# 01_MAIN.net
KiCad netlist of a schematic drawn in Altium Designer
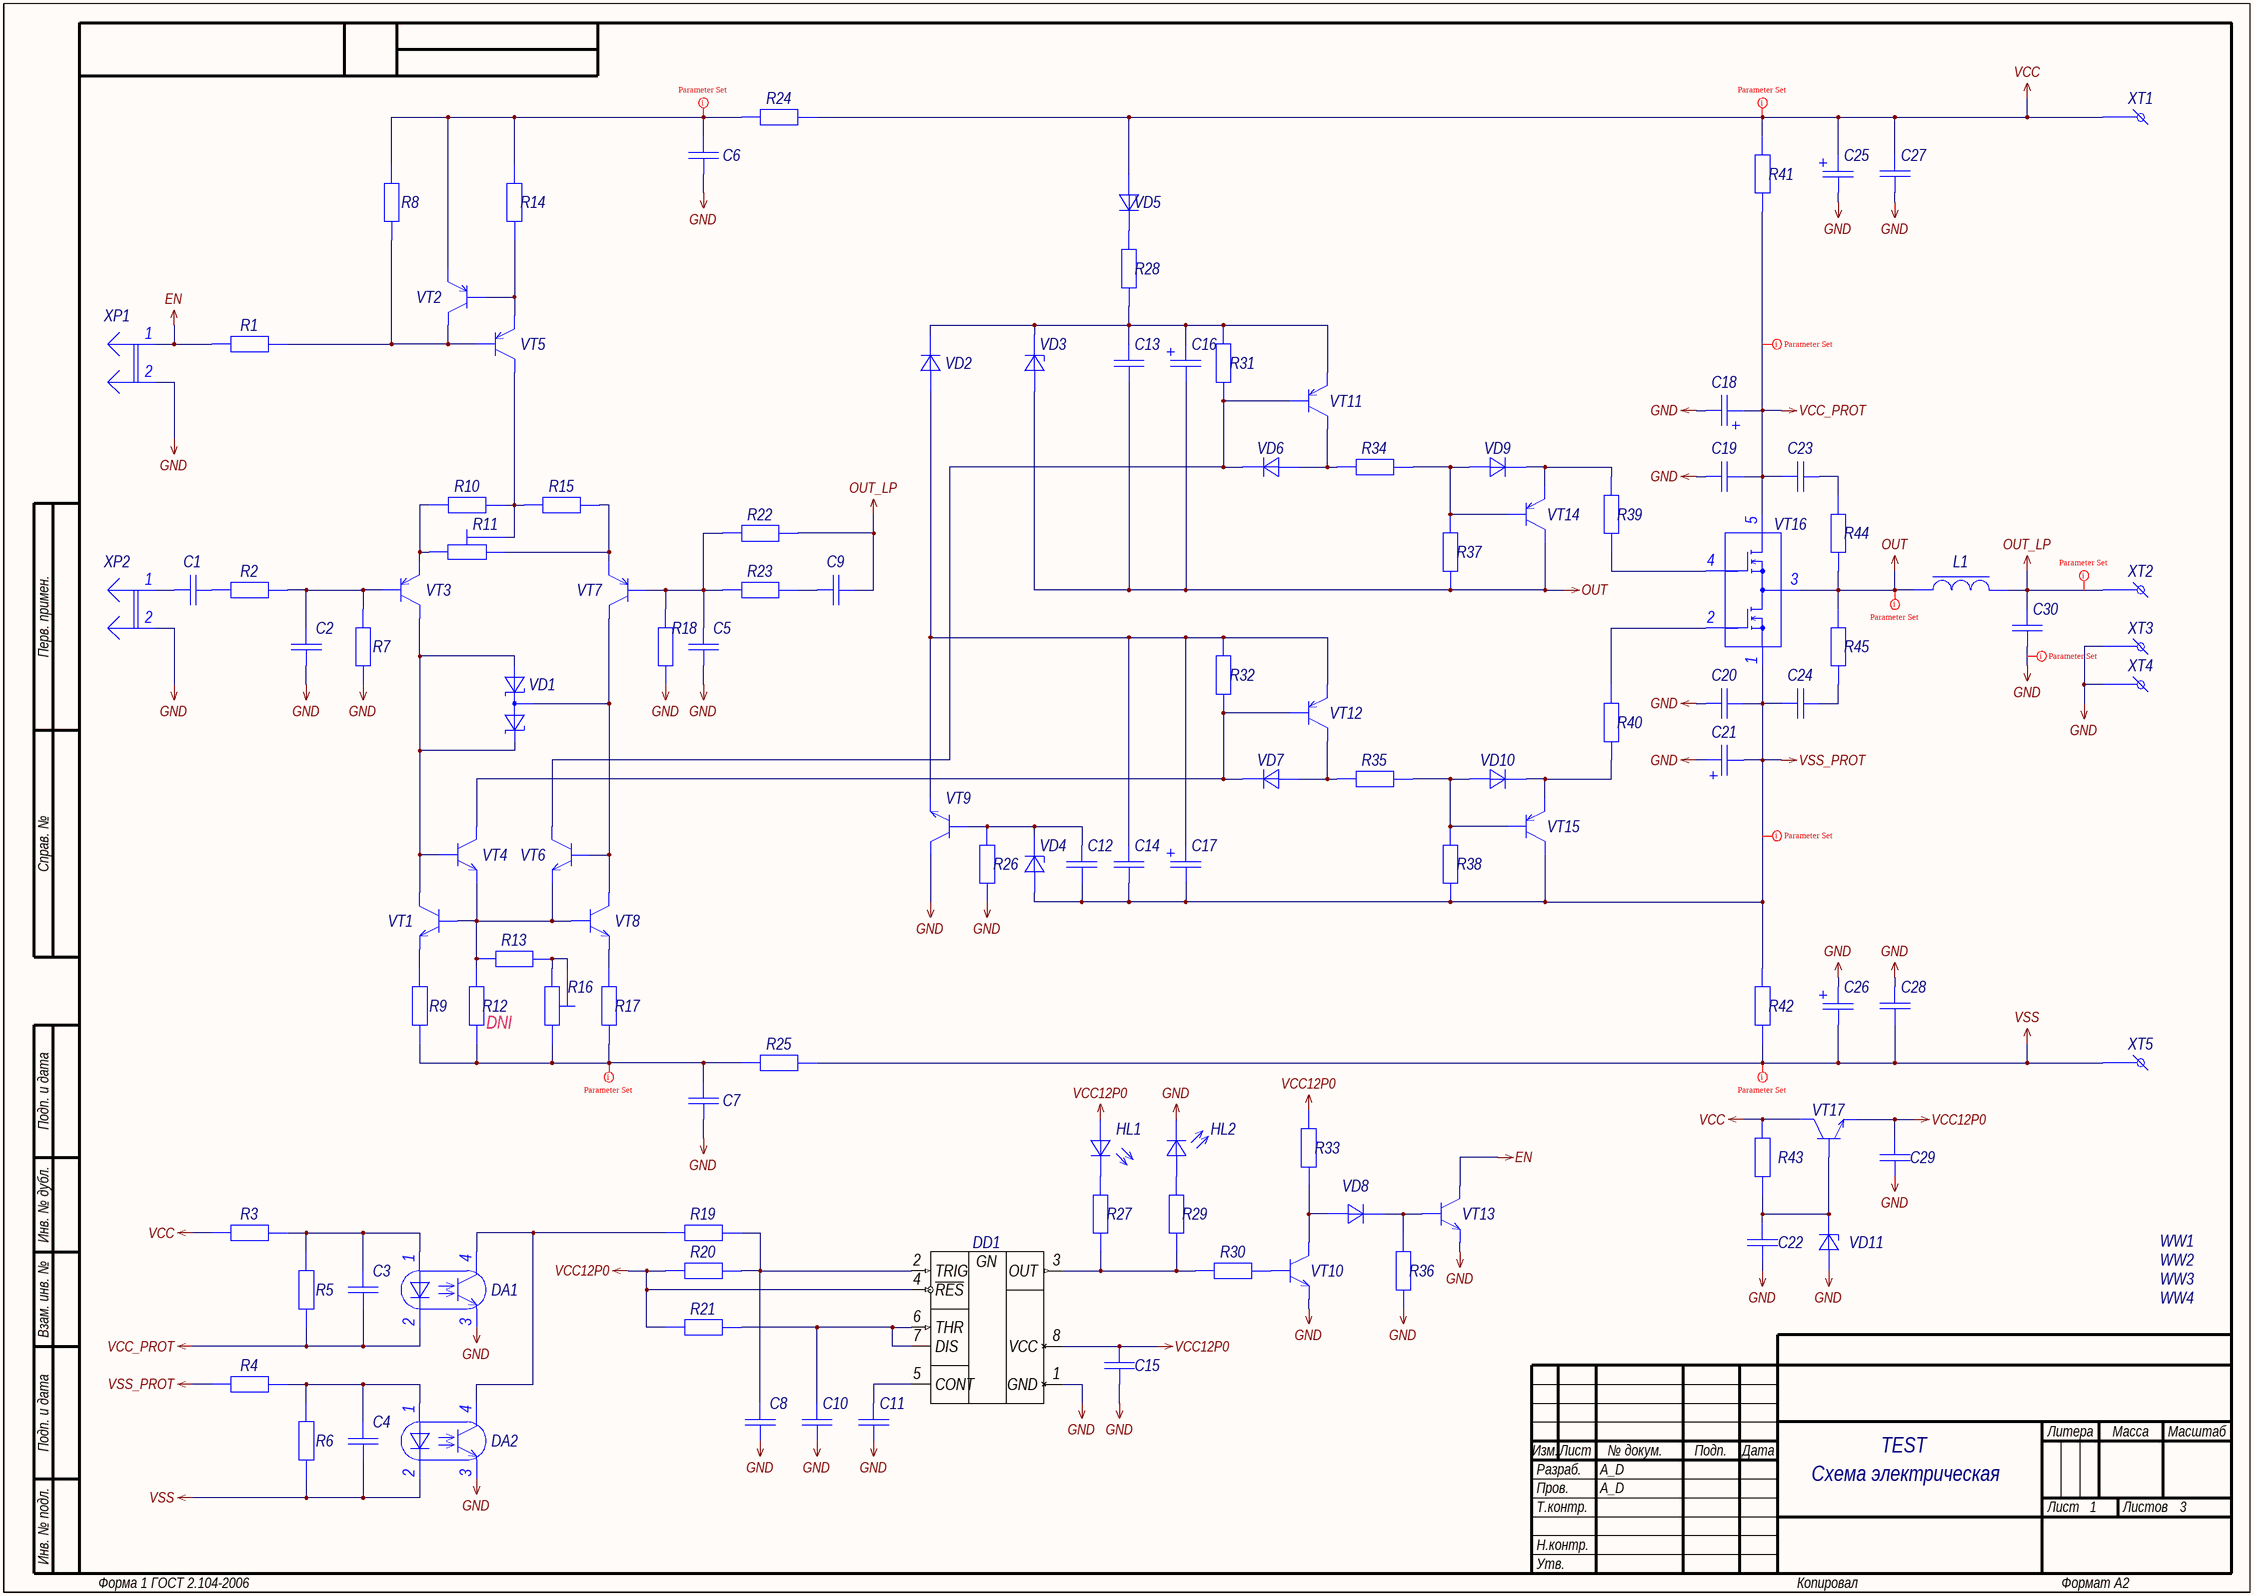
[diagram p0: 01_MAIN.SchDoc]

(export (version "E")
  (design (tool "Eeschema 10.0.6"))
  (components
    (comp (ref "C1")
      (value "Capacitor")
      (footprint "CAPF_050D500P720X500X1000")
      (fields
        (field (name "PART NUMBER") "MKS2B042201F00JSSD")
        (field (name "VOLTAGE") "50V")
        (field (name "TOLERANCE") "±5%")
      )
      (libsource (lib "ADLib") (part "Capacitor"))
    )
    (comp (ref "C2")
      (value "Capacitor")
      (footprint "CAPF_050D500P720X450X600")
      (fields
        (field (name "PART NUMBER") "FKP2D001001D00JSSD")
        (field (name "VOLTAGE") "100V")
        (field (name "TOLERANCE") "±5%")
      )
      (libsource (lib "ADLib") (part "Capacitor"))
    )
    (comp (ref "C3")
      (value "Capacitor")
      (footprint "C0603_L")
      (fields
        (field (name "PART NUMBER") "GRM188R71H182JA01D")
        (field (name "VOLTAGE") "50V")
        (field (name "TOLERANCE") "±5%")
      )
      (libsource (lib "ADLib") (part "Capacitor"))
    )
    (comp (ref "C4")
      (value "Capacitor")
      (footprint "C0603_L")
      (fields
        (field (name "PART NUMBER") "GRM188R71H182JA01D")
        (field (name "VOLTAGE") "50V")
        (field (name "TOLERANCE") "±5%")
      )
      (libsource (lib "ADLib") (part "Capacitor"))
    )
    (comp (ref "C5")
      (value "Capacitor")
      (footprint "C0603_L")
      (fields
        (field (name "PART NUMBER") "GRM1885C1H220JA01D")
        (field (name "VOLTAGE") "50V")
        (field (name "TOLERANCE") "±5%")
      )
      (libsource (lib "ADLib") (part "Capacitor"))
    )
    (comp (ref "C6")
      (value "Capacitor")
      (footprint "C0805_L")
      (fields
        (field (name "PART NUMBER") "GCJ21BR72A104KA01L")
        (field (name "VOLTAGE") "100V")
        (field (name "TOLERANCE") "±10%")
      )
      (libsource (lib "ADLib") (part "Capacitor"))
    )
    (comp (ref "C7")
      (value "Capacitor")
      (footprint "C0805_L")
      (fields
        (field (name "PART NUMBER") "GCJ21BR72A104KA01L")
        (field (name "VOLTAGE") "100V")
        (field (name "TOLERANCE") "±10%")
      )
      (libsource (lib "ADLib") (part "Capacitor"))
    )
    (comp (ref "C8")
      (value "Capacitor")
      (footprint "C0603_L")
      (fields
        (field (name "PART NUMBER") "GCJ188R71C474KA12D")
        (field (name "VOLTAGE") "16V")
        (field (name "TOLERANCE") "±10%")
      )
      (libsource (lib "ADLib") (part "Capacitor"))
    )
    (comp (ref "C9")
      (value "Capacitor")
      (footprint "C0603_L")
      (fields
        (field (name "PART NUMBER") "GRM1885C1H220JA01D")
        (field (name "VOLTAGE") "50V")
        (field (name "TOLERANCE") "±5%")
      )
      (libsource (lib "ADLib") (part "Capacitor"))
    )
    (comp (ref "C10")
      (value "Capacitor")
      (footprint "C0603_L")
      (fields
        (field (name "PART NUMBER") "GCM188R71E105KA64D")
        (field (name "VOLTAGE") "25V")
        (field (name "TOLERANCE") "±10%")
      )
      (libsource (lib "ADLib") (part "Capacitor"))
    )
    (comp (ref "C11")
      (value "Capacitor")
      (footprint "C0603_L")
      (fields
        (field (name "PART NUMBER") "GCM188R71E105KA64D")
        (field (name "VOLTAGE") "25V")
        (field (name "TOLERANCE") "±10%")
      )
      (libsource (lib "ADLib") (part "Capacitor"))
    )
    (comp (ref "C12")
      (value "Capacitor")
      (footprint "C0603_L")
      (fields
        (field (name "PART NUMBER") "GCM188R71E105KA64D")
        (field (name "VOLTAGE") "25V")
        (field (name "TOLERANCE") "±10%")
      )
      (libsource (lib "ADLib") (part "Capacitor"))
    )
    (comp (ref "C13")
      (value "Capacitor")
      (footprint "C0805_L")
      (fields
        (field (name "PART NUMBER") "GCJ21BR72A104KA01L")
        (field (name "VOLTAGE") "100V")
        (field (name "TOLERANCE") "±10%")
      )
      (libsource (lib "ADLib") (part "Capacitor"))
    )
    (comp (ref "C14")
      (value "Capacitor")
      (footprint "C0805_L")
      (fields
        (field (name "PART NUMBER") "GCJ21BR72A104KA01L")
        (field (name "VOLTAGE") "100V")
        (field (name "TOLERANCE") "±10%")
      )
      (libsource (lib "ADLib") (part "Capacitor"))
    )
    (comp (ref "C15")
      (value "Capacitor")
      (footprint "C0603_L")
      (fields
        (field (name "PART NUMBER") "GCJ188R71C474KA12D")
        (field (name "VOLTAGE") "16V")
        (field (name "TOLERANCE") "±10%")
      )
      (libsource (lib "ADLib") (part "Capacitor"))
    )
    (comp (ref "C16")
      (value "Capacitor-E")
      (footprint "CAPE_040D250P630X1100")
      (fields
        (field (name "PART NUMBER") "TKR101M1VE11")
        (field (name "VOLTAGE") "35V")
        (field (name "TOLERANCE") "±20%")
      )
      (libsource (lib "ADLib") (part "Capacitor-E"))
    )
    (comp (ref "C17")
      (value "Capacitor-E")
      (footprint "CAPE_040D250P630X1100")
      (fields
        (field (name "PART NUMBER") "TKR101M1VE11")
        (field (name "VOLTAGE") "35V")
        (field (name "TOLERANCE") "±20%")
      )
      (libsource (lib "ADLib") (part "Capacitor-E"))
    )
    (comp (ref "C18")
      (value "Capacitor-E")
      (footprint "CAPE_040D200P500X1100")
      (fields
        (field (name "PART NUMBER") "TKR220M1JD11")
        (field (name "VOLTAGE") "63V")
        (field (name "TOLERANCE") "±20%")
      )
      (libsource (lib "ADLib") (part "Capacitor-E"))
    )
    (comp (ref "C19")
      (value "Capacitor")
      (footprint "C0805_L")
      (fields
        (field (name "PART NUMBER") "GCJ21BR72A104KA01L")
        (field (name "VOLTAGE") "100V")
        (field (name "TOLERANCE") "±10%")
      )
      (libsource (lib "ADLib") (part "Capacitor"))
    )
    (comp (ref "C20")
      (value "Capacitor")
      (footprint "C0805_L")
      (fields
        (field (name "PART NUMBER") "GCJ21BR72A104KA01L")
        (field (name "VOLTAGE") "100V")
        (field (name "TOLERANCE") "±10%")
      )
      (libsource (lib "ADLib") (part "Capacitor"))
    )
    (comp (ref "C21")
      (value "Capacitor-E")
      (footprint "CAPE_040D200P500X1100")
      (fields
        (field (name "PART NUMBER") "TKR220M1JD11")
        (field (name "VOLTAGE") "63V")
        (field (name "TOLERANCE") "±20%")
      )
      (libsource (lib "ADLib") (part "Capacitor-E"))
    )
    (comp (ref "C22")
      (value "Capacitor")
      (footprint "C0603_L")
      (fields
        (field (name "PART NUMBER") "GCM188R71E105KA64D")
        (field (name "VOLTAGE") "25V")
        (field (name "TOLERANCE") "±10%")
      )
      (libsource (lib "ADLib") (part "Capacitor"))
    )
    (comp (ref "C23")
      (value "Capacitor")
      (footprint "C0603_L")
      (fields
        (field (name "PART NUMBER") "GCM1885C2A101JA16D")
        (field (name "VOLTAGE") "100V")
        (field (name "TOLERANCE") "±5%")
      )
      (libsource (lib "ADLib") (part "Capacitor"))
    )
    (comp (ref "C24")
      (value "Capacitor")
      (footprint "C0603_L")
      (fields
        (field (name "PART NUMBER") "GCM1885C2A101JA16D")
        (field (name "VOLTAGE") "100V")
        (field (name "TOLERANCE") "±5%")
      )
      (libsource (lib "ADLib") (part "Capacitor"))
    )
    (comp (ref "C25")
      (value "Capacitor-E")
      (footprint "CAPE_060D500P1000X2000")
      (fields
        (field (name "PART NUMBER") "TKR471M1HG20")
        (field (name "VOLTAGE") "50V")
        (field (name "TOLERANCE") "±20%")
      )
      (libsource (lib "ADLib") (part "Capacitor-E"))
    )
    (comp (ref "C26")
      (value "Capacitor-E")
      (footprint "CAPE_060D500P1000X2000")
      (fields
        (field (name "PART NUMBER") "TKR471M1HG20")
        (field (name "VOLTAGE") "50V")
        (field (name "TOLERANCE") "±20%")
      )
      (libsource (lib "ADLib") (part "Capacitor-E"))
    )
    (comp (ref "C27")
      (value "Capacitor")
      (footprint "C0805_L")
      (fields
        (field (name "PART NUMBER") "GCJ21BR72A104KA01L")
        (field (name "VOLTAGE") "100V")
        (field (name "TOLERANCE") "±10%")
      )
      (libsource (lib "ADLib") (part "Capacitor"))
    )
    (comp (ref "C28")
      (value "Capacitor")
      (footprint "C0805_L")
      (fields
        (field (name "PART NUMBER") "GCJ21BR72A104KA01L")
        (field (name "VOLTAGE") "100V")
        (field (name "TOLERANCE") "±10%")
      )
      (libsource (lib "ADLib") (part "Capacitor"))
    )
    (comp (ref "C29")
      (value "Capacitor")
      (footprint "C0805_L")
      (fields
        (field (name "PART NUMBER") "GRM21BR61E106KA73L")
        (field (name "VOLTAGE") "25V")
        (field (name "TOLERANCE") "±10%")
      )
      (libsource (lib "ADLib") (part "Capacitor"))
    )
    (comp (ref "C30")
      (value "Capacitor")
      (footprint "CAPF_080D1500P1800X600X1250")
      (fields
        (field (name "PART NUMBER") "MKS4D036804C00KSP1")
        (field (name "VOLTAGE") "100V")
        (field (name "TOLERANCE") "±5%")
      )
      (libsource (lib "ADLib") (part "Capacitor"))
    )
    (comp (ref "DA1")
      (value "Photocoupler-4p")
      (footprint "SOP-4_254P430X440X200_N")
      (fields (field (name "PART NUMBER") "SFH690CT") (field (name "MANUFACTURER") "Vishay Semiconductors"))
      (libsource (lib "ADLib") (part "Photocoupler-4p"))
    )
    (comp (ref "DA2")
      (value "Photocoupler-4p")
      (footprint "SOP-4_254P430X440X200_N")
      (fields (field (name "PART NUMBER") "SFH690CT") (field (name "MANUFACTURER") "Vishay Semiconductors"))
      (libsource (lib "ADLib") (part "Photocoupler-4p"))
    )
    (comp (ref "DD1")
      (value "TIM-555")
      (footprint "SOIC-8_127P490X391X155_N")
      (fields (field (name "PART NUMBER") "NE555D") (field (name "MANUFACTURER") "Texas Instruments"))
      (libsource (lib "ADLib") (part "TIM-555"))
    )
    (comp (ref "HL1")
      (value "ON")
      (footprint "LD0603")
      (fields (field (name "PART NUMBER") "BL-LS0603GC"))
      (libsource (lib "ADLib") (part "Led-1"))
    )
    (comp (ref "HL2")
      (value "PROT")
      (footprint "LD0603")
      (fields (field (name "PART NUMBER") "BL-LS0603EC"))
      (libsource (lib "ADLib") (part "Led-1"))
    )
    (comp (ref "L1")
      (value "Coil")
      (footprint "B82477G4-Series")
      (fields
        (field (name "PART NUMBER") "B82477G4103M000")
        (field (name "TOLERANCE") "±20%")
        (field (name "MANUFACTURER") "Epcos")
      )
      (libsource (lib "ADLib") (part "Coil"))
    )
    (comp (ref "R1")
      (value "Resistor")
      (footprint "R0603_L")
      (fields
        (field (name "PART NUMBER") "RC0603JR-0747KL")
        (field (name "TOLERANCE") "±5%")
        (field (name "MANUFACTURER") "Yageo")
      )
      (libsource (lib "ADLib") (part "Resistor"))
    )
    (comp (ref "R2")
      (value "Resistor")
      (footprint "R0603_L")
      (fields
        (field (name "PART NUMBER") "RC0603JR-071KL")
        (field (name "TOLERANCE") "±5%")
        (field (name "MANUFACTURER") "Yageo")
      )
      (libsource (lib "ADLib") (part "Resistor"))
    )
    (comp (ref "R3")
      (value "Resistor")
      (footprint "R0603_L")
      (fields
        (field (name "PART NUMBER") "RC0603JR-07470R")
        (field (name "TOLERANCE") "±5%")
        (field (name "MANUFACTURER") "Yageo")
      )
      (libsource (lib "ADLib") (part "Resistor"))
    )
    (comp (ref "R4")
      (value "Resistor")
      (footprint "R0603_L")
      (fields
        (field (name "PART NUMBER") "RC0603JR-07470R")
        (field (name "TOLERANCE") "±5%")
        (field (name "MANUFACTURER") "Yageo")
      )
      (libsource (lib "ADLib") (part "Resistor"))
    )
    (comp (ref "R5")
      (value "Resistor")
      (footprint "R0603_L")
      (fields
        (field (name "PART NUMBER") "RC0603JR-0710KL")
        (field (name "TOLERANCE") "±5%")
        (field (name "MANUFACTURER") "Yageo")
      )
      (libsource (lib "ADLib") (part "Resistor"))
    )
    (comp (ref "R6")
      (value "Resistor")
      (footprint "R0603_L")
      (fields
        (field (name "PART NUMBER") "RC0603JR-0710KL")
        (field (name "TOLERANCE") "±5%")
        (field (name "MANUFACTURER") "Yageo")
      )
      (libsource (lib "ADLib") (part "Resistor"))
    )
    (comp (ref "R7")
      (value "Resistor")
      (footprint "R0603_L")
      (fields
        (field (name "PART NUMBER") "RC0603JR-071K5L")
        (field (name "TOLERANCE") "±5%")
        (field (name "MANUFACTURER") "Yageo")
      )
      (libsource (lib "ADLib") (part "Resistor"))
    )
    (comp (ref "R8")
      (value "Resistor")
      (footprint "R0603_L")
      (fields
        (field (name "PART NUMBER") "RC0603JR-0747KL")
        (field (name "TOLERANCE") "±5%")
        (field (name "MANUFACTURER") "Yageo")
      )
      (libsource (lib "ADLib") (part "Resistor"))
    )
    (comp (ref "R9")
      (value "Resistor")
      (footprint "R0603_L")
      (fields
        (field (name "PART NUMBER") "RC0603JR-0751RL")
        (field (name "TOLERANCE") "±5%")
        (field (name "MANUFACTURER") "Yageo")
      )
      (libsource (lib "ADLib") (part "Resistor"))
    )
    (comp (ref "R10")
      (value "Resistor")
      (footprint "R0603_L")
      (fields
        (field (name "PART NUMBER") "RC0603JR-0747RL")
        (field (name "TOLERANCE") "±5%")
        (field (name "MANUFACTURER") "Yageo")
      )
      (libsource (lib "ADLib") (part "Resistor"))
    )
    (comp (ref "R11")
      (value "Resistor-Trimmer-1")
      (footprint "3266W")
      (fields
        (field (name "PART NUMBER") "3266W-1-501")
        (field (name "TOLERANCE") "±10%")
        (field (name "MANUFACTURER") "Bourns")
      )
      (libsource (lib "ADLib") (part "Resistor-Trimmer-1"))
    )
    (comp (ref "R12")
      (value "Resistor")
      (footprint "R0603_L")
      (fields
        (field (name "PART NUMBER") "RC0603JR-07330RL")
        (field (name "TOLERANCE") "±5%")
        (field (name "MANUFACTURER") "Yageo")
      )
      (libsource (lib "ADLib") (part "Resistor"))
    )
    (comp (ref "R13")
      (value "Resistor")
      (footprint "R0603_L")
      (fields
        (field (name "PART NUMBER") "RC0603JR-07100R")
        (field (name "TOLERANCE") "±5%")
        (field (name "MANUFACTURER") "Yageo")
      )
      (libsource (lib "ADLib") (part "Resistor"))
    )
    (comp (ref "R14")
      (value "Resistor")
      (footprint "R0603_L")
      (fields
        (field (name "PART NUMBER") "RC0603JR-07220R")
        (field (name "TOLERANCE") "±5%")
        (field (name "MANUFACTURER") "Yageo")
      )
      (libsource (lib "ADLib") (part "Resistor"))
    )
    (comp (ref "R15")
      (value "Resistor")
      (footprint "R0603_L")
      (fields
        (field (name "PART NUMBER") "RC0603JR-0747RL")
        (field (name "TOLERANCE") "±5%")
        (field (name "MANUFACTURER") "Yageo")
      )
      (libsource (lib "ADLib") (part "Resistor"))
    )
    (comp (ref "R16")
      (value "Resistor-Trimmer-1")
      (footprint "3266W")
      (fields
        (field (name "PART NUMBER") "3266W-1-502")
        (field (name "TOLERANCE") "±10%")
        (field (name "MANUFACTURER") "Bourns")
      )
      (libsource (lib "ADLib") (part "Resistor-Trimmer-1"))
    )
    (comp (ref "R17")
      (value "Resistor")
      (footprint "R0603_L")
      (fields
        (field (name "PART NUMBER") "RC0603JR-0751RL")
        (field (name "TOLERANCE") "±5%")
        (field (name "MANUFACTURER") "Yageo")
      )
      (libsource (lib "ADLib") (part "Resistor"))
    )
    (comp (ref "R18")
      (value "Resistor")
      (footprint "R0603_L")
      (fields
        (field (name "PART NUMBER") "RC0603JR-071K5L")
        (field (name "TOLERANCE") "±5%")
        (field (name "MANUFACTURER") "Yageo")
      )
      (libsource (lib "ADLib") (part "Resistor"))
    )
    (comp (ref "R19")
      (value "Resistor")
      (footprint "R0603_L")
      (fields
        (field (name "PART NUMBER") "RC0603JR-0710RL")
        (field (name "TOLERANCE") "±5%")
        (field (name "MANUFACTURER") "Yageo")
      )
      (libsource (lib "ADLib") (part "Resistor"))
    )
    (comp (ref "R20")
      (value "Resistor")
      (footprint "R0603_L")
      (fields
        (field (name "PART NUMBER") "RC0603JR-071ML")
        (field (name "TOLERANCE") "±5%")
        (field (name "MANUFACTURER") "Yageo")
      )
      (libsource (lib "ADLib") (part "Resistor"))
    )
    (comp (ref "R21")
      (value "Resistor")
      (footprint "R0603_L")
      (fields
        (field (name "PART NUMBER") "RC0603JR-071ML")
        (field (name "TOLERANCE") "±5%")
        (field (name "MANUFACTURER") "Yageo")
      )
      (libsource (lib "ADLib") (part "Resistor"))
    )
    (comp (ref "R22")
      (value "Resistor")
      (footprint "R0603_L")
      (fields
        (field (name "PART NUMBER") "RC0603JR-078K2L")
        (field (name "TOLERANCE") "±5%")
        (field (name "MANUFACTURER") "Yageo")
      )
      (libsource (lib "ADLib") (part "Resistor"))
    )
    (comp (ref "R23")
      (value "Resistor")
      (footprint "R0603_L")
      (fields
        (field (name "PART NUMBER") "RC0603JR-071KL")
        (field (name "TOLERANCE") "±5%")
        (field (name "MANUFACTURER") "Yageo")
      )
      (libsource (lib "ADLib") (part "Resistor"))
    )
    (comp (ref "R24")
      (value "Resistor")
      (footprint "R0805_L")
      (fields
        (field (name "PART NUMBER") "RC0805JR-0710RL")
        (field (name "TOLERANCE") "±5%")
        (field (name "MANUFACTURER") "Yageo")
      )
      (libsource (lib "ADLib") (part "Resistor"))
    )
    (comp (ref "R25")
      (value "Resistor")
      (footprint "R0805_L")
      (fields
        (field (name "PART NUMBER") "RC0805JR-0710RL")
        (field (name "TOLERANCE") "±5%")
        (field (name "MANUFACTURER") "Yageo")
      )
      (libsource (lib "ADLib") (part "Resistor"))
    )
    (comp (ref "R26")
      (value "Resistor")
      (footprint "R0603_L")
      (fields
        (field (name "PART NUMBER") "RC0603JR-078K2L")
        (field (name "TOLERANCE") "±5%")
        (field (name "MANUFACTURER") "Yageo")
      )
      (libsource (lib "ADLib") (part "Resistor"))
    )
    (comp (ref "R27")
      (value "Resistor")
      (footprint "R0603_L")
      (fields
        (field (name "PART NUMBER") "RC0603JR-072K2L")
        (field (name "TOLERANCE") "±5%")
        (field (name "MANUFACTURER") "Yageo")
      )
      (libsource (lib "ADLib") (part "Resistor"))
    )
    (comp (ref "R28")
      (value "Resistor")
      (footprint "R0603_L")
      (fields
        (field (name "PART NUMBER") "RC0603JR-074K7L")
        (field (name "TOLERANCE") "±5%")
        (field (name "MANUFACTURER") "Yageo")
      )
      (libsource (lib "ADLib") (part "Resistor"))
    )
    (comp (ref "R29")
      (value "Resistor")
      (footprint "R0603_L")
      (fields
        (field (name "PART NUMBER") "RC0603JR-072K2L")
        (field (name "TOLERANCE") "±5%")
        (field (name "MANUFACTURER") "Yageo")
      )
      (libsource (lib "ADLib") (part "Resistor"))
    )
    (comp (ref "R30")
      (value "Resistor")
      (footprint "R0603_L")
      (fields
        (field (name "PART NUMBER") "RC0603JR-0710KL")
        (field (name "TOLERANCE") "±5%")
        (field (name "MANUFACTURER") "Yageo")
      )
      (libsource (lib "ADLib") (part "Resistor"))
    )
    (comp (ref "R31")
      (value "Resistor")
      (footprint "R0603_L")
      (fields
        (field (name "PART NUMBER") "RC0603JR-07470R")
        (field (name "TOLERANCE") "±5%")
        (field (name "MANUFACTURER") "Yageo")
      )
      (libsource (lib "ADLib") (part "Resistor"))
    )
    (comp (ref "R32")
      (value "Resistor")
      (footprint "R0603_L")
      (fields
        (field (name "PART NUMBER") "RC0603JR-07470R")
        (field (name "TOLERANCE") "±5%")
        (field (name "MANUFACTURER") "Yageo")
      )
      (libsource (lib "ADLib") (part "Resistor"))
    )
    (comp (ref "R33")
      (value "Resistor")
      (footprint "R0603_L")
      (fields
        (field (name "PART NUMBER") "RC0603JR-0722KL")
        (field (name "TOLERANCE") "±5%")
        (field (name "MANUFACTURER") "Yageo")
      )
      (libsource (lib "ADLib") (part "Resistor"))
    )
    (comp (ref "R34")
      (value "Resistor")
      (footprint "R0603_L")
      (fields
        (field (name "PART NUMBER") "RC0603JR-0730RL")
        (field (name "TOLERANCE") "±5%")
        (field (name "MANUFACTURER") "Yageo")
      )
      (libsource (lib "ADLib") (part "Resistor"))
    )
    (comp (ref "R35")
      (value "Resistor")
      (footprint "R0603_L")
      (fields
        (field (name "PART NUMBER") "RC0603JR-0730RL")
        (field (name "TOLERANCE") "±5%")
        (field (name "MANUFACTURER") "Yageo")
      )
      (libsource (lib "ADLib") (part "Resistor"))
    )
    (comp (ref "R36")
      (value "Resistor")
      (footprint "R0603_L")
      (fields
        (field (name "PART NUMBER") "RC0603JR-0710KL")
        (field (name "TOLERANCE") "±5%")
        (field (name "MANUFACTURER") "Yageo")
      )
      (libsource (lib "ADLib") (part "Resistor"))
    )
    (comp (ref "R37")
      (value "Resistor")
      (footprint "R0603_L")
      (fields
        (field (name "PART NUMBER") "RC0603FR-07390RL")
        (field (name "TOLERANCE") "±1%")
        (field (name "MANUFACTURER") "Yageo")
      )
      (libsource (lib "ADLib") (part "Resistor"))
    )
    (comp (ref "R38")
      (value "Resistor")
      (footprint "R0603_L")
      (fields
        (field (name "PART NUMBER") "RC0603FR-07390RL")
        (field (name "TOLERANCE") "±1%")
        (field (name "MANUFACTURER") "Yageo")
      )
      (libsource (lib "ADLib") (part "Resistor"))
    )
    (comp (ref "R39")
      (value "Resistor")
      (footprint "R0603_L")
      (fields
        (field (name "PART NUMBER") "RC0603JR-070R")
        (field (name "TOLERANCE") "±5%")
        (field (name "MANUFACTURER") "Yageo")
      )
      (libsource (lib "ADLib") (part "Resistor"))
    )
    (comp (ref "R40")
      (value "Resistor")
      (footprint "R0603_L")
      (fields
        (field (name "PART NUMBER") "RC0603JR-070R")
        (field (name "TOLERANCE") "±5%")
        (field (name "MANUFACTURER") "Yageo")
      )
      (libsource (lib "ADLib") (part "Resistor"))
    )
    (comp (ref "R41")
      (value "Resistor")
      (footprint "R2512_L")
      (fields
        (field (name "PART NUMBER") "RL2512FK-070R33L")
        (field (name "TOLERANCE") "±1%")
        (field (name "MANUFACTURER") "Yageo")
      )
      (libsource (lib "ADLib") (part "Resistor"))
    )
    (comp (ref "R42")
      (value "Resistor")
      (footprint "R2512_L")
      (fields
        (field (name "PART NUMBER") "RL2512FK-070R33L")
        (field (name "TOLERANCE") "±1%")
        (field (name "MANUFACTURER") "Yageo")
      )
      (libsource (lib "ADLib") (part "Resistor"))
    )
    (comp (ref "R43")
      (value "Resistor")
      (footprint "R0603_L")
      (fields
        (field (name "PART NUMBER") "RC0603JR-078K2L")
        (field (name "TOLERANCE") "±5%")
        (field (name "MANUFACTURER") "Yageo")
      )
      (libsource (lib "ADLib") (part "Resistor"))
    )
    (comp (ref "R44")
      (value "Resistor")
      (footprint "R0805_L")
      (fields
        (field (name "PART NUMBER") "RC0805JR-0710RL")
        (field (name "TOLERANCE") "±5%")
        (field (name "MANUFACTURER") "Yageo")
      )
      (libsource (lib "ADLib") (part "Resistor"))
    )
    (comp (ref "R45")
      (value "Resistor")
      (footprint "R0805_L")
      (fields
        (field (name "PART NUMBER") "RC0805JR-0710RL")
        (field (name "TOLERANCE") "±5%")
        (field (name "MANUFACTURER") "Yageo")
      )
      (libsource (lib "ADLib") (part "Resistor"))
    )
    (comp (ref "VD1")
      (value "Schottky_AC")
      (footprint "SOT-23_190P290X160X145_N")
      (fields (field (name "PART NUMBER") "BAT54S") (field (name "MANUFACTURER") "NXP Semiconductors"))
      (libsource (lib "ADLib") (part "Schottky_AC"))
    )
    (comp (ref "VD2")
      (value "Diode")
      (footprint "SOD-323")
      (fields (field (name "PART NUMBER") "BAS316") (field (name "MANUFACTURER") "NXP"))
      (libsource (lib "ADLib") (part "Diode"))
    )
    (comp (ref "VD3")
      (value "Zener")
      (footprint "SOD-323")
      (fields (field (name "PART NUMBER") "BZX384-C12") (field (name "MANUFACTURER") "NXP"))
      (libsource (lib "ADLib") (part "Zener"))
    )
    (comp (ref "VD4")
      (value "Zener")
      (footprint "SOD-323")
      (fields (field (name "PART NUMBER") "BZX384-C12") (field (name "MANUFACTURER") "NXP"))
      (libsource (lib "ADLib") (part "Zener"))
    )
    (comp (ref "VD5")
      (value "Diode")
      (footprint "SOD-323")
      (fields (field (name "PART NUMBER") "1N4148WS-7-F") (field (name "MANUFACTURER") "Diodes Incorporated"))
      (libsource (lib "ADLib") (part "Diode"))
    )
    (comp (ref "VD6")
      (value "Diode")
      (footprint "SOD-323")
      (fields (field (name "PART NUMBER") "BAS316") (field (name "MANUFACTURER") "NXP"))
      (libsource (lib "ADLib") (part "Diode"))
    )
    (comp (ref "VD7")
      (value "Diode")
      (footprint "SOD-323")
      (fields (field (name "PART NUMBER") "BAS316") (field (name "MANUFACTURER") "NXP"))
      (libsource (lib "ADLib") (part "Diode"))
    )
    (comp (ref "VD8")
      (value "Diode")
      (footprint "SOD-323")
      (fields (field (name "PART NUMBER") "1N4148WS-7-F") (field (name "MANUFACTURER") "Diodes Incorporated"))
      (libsource (lib "ADLib") (part "Diode"))
    )
    (comp (ref "VD9")
      (value "Diode")
      (footprint "SOD-323")
      (fields (field (name "PART NUMBER") "BAS316") (field (name "MANUFACTURER") "NXP"))
      (libsource (lib "ADLib") (part "Diode"))
    )
    (comp (ref "VD10")
      (value "Diode")
      (footprint "SOD-323")
      (fields (field (name "PART NUMBER") "BAS316") (field (name "MANUFACTURER") "NXP"))
      (libsource (lib "ADLib") (part "Diode"))
    )
    (comp (ref "VD11")
      (value "Zener")
      (footprint "SOD-323")
      (fields (field (name "PART NUMBER") "BZX384-C12") (field (name "MANUFACTURER") "NXP"))
      (libsource (lib "ADLib") (part "Zener"))
    )
    (comp (ref "VT1")
      (value "BJT-NPN")
      (footprint "SOT-23_190P290X160X145_N")
      (fields (field (name "PART NUMBER") "BC847"))
      (libsource (lib "ADLib") (part "BJT-NPN"))
    )
    (comp (ref "VT2")
      (value "BJT-PNP")
      (footprint "SOT-23_190P290X160X145_N")
      (fields (field (name "PART NUMBER") "BC857"))
      (libsource (lib "ADLib") (part "BJT-PNP"))
    )
    (comp (ref "VT3")
      (value "BJT-PNP")
      (footprint "SOT-23_190P290X160X145_N")
      (fields (field (name "PART NUMBER") "MMBT5401"))
      (libsource (lib "ADLib") (part "BJT-PNP"))
    )
    (comp (ref "VT4")
      (value "BJT-NPN")
      (footprint "SOT-23_190P290X160X145_N")
      (fields (field (name "PART NUMBER") "MMBT5551"))
      (libsource (lib "ADLib") (part "BJT-NPN"))
    )
    (comp (ref "VT5")
      (value "BJT-PNP")
      (footprint "SOT-89_150P460X260X170_N")
      (fields (field (name "PART NUMBER") "BCX53"))
      (libsource (lib "ADLib") (part "BJT-PNP"))
    )
    (comp (ref "VT6")
      (value "BJT-NPN")
      (footprint "SOT-23_190P290X160X145_N")
      (fields (field (name "PART NUMBER") "MMBT5551"))
      (libsource (lib "ADLib") (part "BJT-NPN"))
    )
    (comp (ref "VT7")
      (value "BJT-PNP")
      (footprint "SOT-23_190P290X160X145_N")
      (fields (field (name "PART NUMBER") "MMBT5401"))
      (libsource (lib "ADLib") (part "BJT-PNP"))
    )
    (comp (ref "VT8")
      (value "BJT-NPN")
      (footprint "SOT-23_190P290X160X145_N")
      (fields (field (name "PART NUMBER") "BC847"))
      (libsource (lib "ADLib") (part "BJT-NPN"))
    )
    (comp (ref "VT9")
      (value "BJT-NPN")
      (footprint "SOT-89_150P460X260X170_N")
      (fields (field (name "PART NUMBER") "BCX56"))
      (libsource (lib "ADLib") (part "BJT-NPN"))
    )
    (comp (ref "VT10")
      (value "BJT-NPN")
      (footprint "SOT-23_190P290X160X145_N")
      (fields (field (name "PART NUMBER") "BC847"))
      (libsource (lib "ADLib") (part "BJT-NPN"))
    )
    (comp (ref "VT11")
      (value "BJT-PNP")
      (footprint "SOT-23_190P290X160X145_N")
      (fields (field (name "PART NUMBER") "BC807") (field (name "MANUFACTURER") "NXP"))
      (libsource (lib "ADLib") (part "BJT-PNP"))
    )
    (comp (ref "VT12")
      (value "BJT-PNP")
      (footprint "SOT-23_190P290X160X145_N")
      (fields (field (name "PART NUMBER") "BC807") (field (name "MANUFACTURER") "NXP"))
      (libsource (lib "ADLib") (part "BJT-PNP"))
    )
    (comp (ref "VT13")
      (value "BJT-NPN")
      (footprint "SOT-23_190P290X160X145_N")
      (fields (field (name "PART NUMBER") "BC847"))
      (libsource (lib "ADLib") (part "BJT-NPN"))
    )
    (comp (ref "VT14")
      (value "BJT-PNP")
      (footprint "SOT-23_190P290X160X145_N")
      (fields (field (name "PART NUMBER") "BC807") (field (name "MANUFACTURER") "NXP"))
      (libsource (lib "ADLib") (part "BJT-PNP"))
    )
    (comp (ref "VT15")
      (value "BJT-PNP")
      (footprint "SOT-23_190P290X160X145_N")
      (fields (field (name "PART NUMBER") "BC807") (field (name "MANUFACTURER") "NXP"))
      (libsource (lib "ADLib") (part "BJT-PNP"))
    )
    (comp (ref "VT16")
      (value "IRFI4212H-117P")
      (footprint "TO-220-5-117-WB")
      (fields (field (name "MANUFACTURER") "Infineon"))
      (libsource (lib "ADLib") (part "IRFI4212H-117P"))
    )
    (comp (ref "VT17")
      (value "BJT-NPN")
      (footprint "SOT-89_150P460X260X170_N")
      (fields (field (name "PART NUMBER") "BCX56"))
      (libsource (lib "ADLib") (part "BJT-NPN"))
    )
    (comp (ref "WW1")
      (value "NoBody")
      (footprint "MH_M3.0")
      (fields (field (name "PART NUMBER") "MOUNTINGHOLE"))
      (libsource (lib "ADLib") (part "NoBody"))
    )
    (comp (ref "WW2")
      (value "NoBody")
      (footprint "MH_M3.0")
      (fields (field (name "PART NUMBER") "MOUNTINGHOLE"))
      (libsource (lib "ADLib") (part "NoBody"))
    )
    (comp (ref "WW3")
      (value "NoBody")
      (footprint "MH_M3.0")
      (fields (field (name "PART NUMBER") "MOUNTINGHOLE"))
      (libsource (lib "ADLib") (part "NoBody"))
    )
    (comp (ref "WW4")
      (value "NoBody")
      (footprint "MH_M3.0")
      (fields (field (name "PART NUMBER") "MOUNTINGHOLE"))
      (libsource (lib "ADLib") (part "NoBody"))
    )
    (comp (ref "XP1")
      (value "EN")
      (footprint "PLS-2")
      (fields (field (name "PART NUMBER") "PLS-2"))
      (libsource (lib "ADLib") (part "Con-2-M"))
    )
    (comp (ref "XP2")
      (value "IN")
      (footprint "PLS-2")
      (fields (field (name "PART NUMBER") "PLS-2"))
      (libsource (lib "ADLib") (part "Con-2-M"))
    )
    (comp (ref "XT1")
      (value "VCC")
      (footprint "62650-1")
      (fields (field (name "PART NUMBER") "62650-1") (field (name "MANUFACTURER") "TE Connectivity"))
      (libsource (lib "ADLib") (part "Con-1-T"))
    )
    (comp (ref "XT2")
      (value "OUT")
      (footprint "62650-1")
      (fields (field (name "PART NUMBER") "62650-1") (field (name "MANUFACTURER") "TE Connectivity"))
      (libsource (lib "ADLib") (part "Con-1-T"))
    )
    (comp (ref "XT3")
      (value "GND")
      (footprint "62650-1")
      (fields (field (name "PART NUMBER") "62650-1") (field (name "MANUFACTURER") "TE Connectivity"))
      (libsource (lib "ADLib") (part "Con-1-T"))
    )
    (comp (ref "XT4")
      (value "GND")
      (footprint "62650-1")
      (fields (field (name "PART NUMBER") "62650-1") (field (name "MANUFACTURER") "TE Connectivity"))
      (libsource (lib "ADLib") (part "Con-1-T"))
    )
    (comp (ref "XT5")
      (value "VSS")
      (footprint "62650-1")
      (fields (field (name "PART NUMBER") "62650-1") (field (name "MANUFACTURER") "TE Connectivity"))
      (libsource (lib "ADLib") (part "Con-1-T"))
    )
  )
  (nets
    (net (code "1") (name "EN") (class "Default")
      (node (ref "R1") (pin "2") (pinfunction "2_2") (pintype "passive"))
      (node (ref "VT13") (pin "2") (pinfunction "К_2") (pintype "passive"))
      (node (ref "XP1") (pin "1") (pintype "passive"))
    )
    (net (code "2") (name "GND") (class "Default")
      (node (ref "C10") (pin "1") (pinfunction "1_1") (pintype "passive"))
      (node (ref "C11") (pin "1") (pinfunction "1_1") (pintype "passive"))
      (node (ref "C15") (pin "1") (pinfunction "1_1") (pintype "passive"))
      (node (ref "C18") (pin "2") (pinfunction "2_2") (pintype "passive"))
      (node (ref "C19") (pin "2") (pinfunction "2_2") (pintype "passive"))
      (node (ref "C2") (pin "1") (pinfunction "1_1") (pintype "passive"))
      (node (ref "C20") (pin "2") (pinfunction "2_2") (pintype "passive"))
      (node (ref "C21") (pin "1") (pinfunction "1_1") (pintype "passive"))
      (node (ref "C22") (pin "1") (pinfunction "1_1") (pintype "passive"))
      (node (ref "C25") (pin "2") (pinfunction "2_2") (pintype "passive"))
      (node (ref "C26") (pin "1") (pinfunction "1_1") (pintype "passive"))
      (node (ref "C27") (pin "2") (pinfunction "2_2") (pintype "passive"))
      (node (ref "C28") (pin "1") (pinfunction "1_1") (pintype "passive"))
      (node (ref "C29") (pin "1") (pinfunction "1_1") (pintype "passive"))
      (node (ref "C30") (pin "1") (pinfunction "1_1") (pintype "passive"))
      (node (ref "C5") (pin "1") (pinfunction "1_1") (pintype "passive"))
      (node (ref "C6") (pin "1") (pinfunction "1_1") (pintype "passive"))
      (node (ref "C7") (pin "1") (pinfunction "1_1") (pintype "passive"))
      (node (ref "C8") (pin "1") (pinfunction "1_1") (pintype "passive"))
      (node (ref "DA1") (pin "3") (pinfunction "Э_3") (pintype "passive"))
      (node (ref "DA2") (pin "3") (pinfunction "Э_3") (pintype "passive"))
      (node (ref "DD1") (pin "1") (pinfunction "GND_1") (pintype "power_in"))
      (node (ref "HL2") (pin "2") (pinfunction "К_2") (pintype "passive"))
      (node (ref "R18") (pin "1") (pinfunction "1_1") (pintype "passive"))
      (node (ref "R26") (pin "1") (pinfunction "1_1") (pintype "passive"))
      (node (ref "R36") (pin "1") (pinfunction "1_1") (pintype "passive"))
      (node (ref "R7") (pin "1") (pinfunction "1_1") (pintype "passive"))
      (node (ref "VD11") (pin "1") (pinfunction "А_1") (pintype "passive"))
      (node (ref "VT10") (pin "3") (pinfunction "Э_3") (pintype "passive"))
      (node (ref "VT13") (pin "3") (pinfunction "Э_3") (pintype "passive"))
      (node (ref "VT9") (pin "2") (pinfunction "К_2") (pintype "passive"))
      (node (ref "XP1") (pin "2") (pintype "passive"))
      (node (ref "XP2") (pin "2") (pintype "passive"))
      (node (ref "XT3") (pin "1") (pintype "passive"))
      (node (ref "XT4") (pin "1") (pintype "passive"))
    )
    (net (code "3") (name "Net-(C1-Pad1)") (class "Default")
      (node (ref "C1") (pin "1") (pinfunction "1_1") (pintype "passive"))
      (node (ref "XP2") (pin "1") (pintype "passive"))
    )
    (net (code "4") (name "Net-(C1-Pad2)") (class "Default")
      (node (ref "C1") (pin "2") (pinfunction "2_2") (pintype "passive"))
      (node (ref "R2") (pin "1") (pinfunction "1_1") (pintype "passive"))
    )
    (net (code "5") (name "Net-(C7-Pad2)") (class "Default")
      (node (ref "C7") (pin "2") (pinfunction "2_2") (pintype "passive"))
      (node (ref "R12") (pin "1") (pinfunction "1_1") (pintype "passive"))
      (node (ref "R16") (pin "3") (pinfunction "3_3") (pintype "passive"))
      (node (ref "R17") (pin "1") (pinfunction "1_1") (pintype "passive"))
      (node (ref "R25") (pin "1") (pinfunction "1_1") (pintype "passive"))
      (node (ref "R9") (pin "1") (pinfunction "1_1") (pintype "passive"))
    )
    (net (code "6") (name "Net-(C9-Pad1)") (class "Default")
      (node (ref "C9") (pin "1") (pinfunction "1_1") (pintype "passive"))
      (node (ref "R23") (pin "2") (pinfunction "2_2") (pintype "passive"))
    )
    (net (code "7") (name "Net-(C23-Pad2)") (class "Default")
      (node (ref "C23") (pin "2") (pinfunction "2_2") (pintype "passive"))
      (node (ref "R44") (pin "2") (pinfunction "2_2") (pintype "passive"))
    )
    (net (code "8") (name "Net-(C24-Pad2)") (class "Default")
      (node (ref "C24") (pin "2") (pinfunction "2_2") (pintype "passive"))
      (node (ref "R45") (pin "1") (pinfunction "1_1") (pintype "passive"))
    )
    (net (code "9") (name "Net-(DA1-CА)") (class "Default")
      (node (ref "C3") (pin "2") (pinfunction "2_2") (pintype "passive"))
      (node (ref "DA1") (pin "1") (pinfunction "CА_1") (pintype "passive"))
      (node (ref "R3") (pin "2") (pinfunction "2_2") (pintype "passive"))
      (node (ref "R5") (pin "2") (pinfunction "2_2") (pintype "passive"))
    )
    (net (code "10") (name "Net-(DA1-К)") (class "Default")
      (node (ref "DA1") (pin "4") (pinfunction "К_4") (pintype "passive"))
      (node (ref "DA2") (pin "4") (pinfunction "К_4") (pintype "passive"))
      (node (ref "R19") (pin "1") (pinfunction "1_1") (pintype "passive"))
    )
    (net (code "11") (name "Net-(DA2-CА)") (class "Default")
      (node (ref "C4") (pin "2") (pinfunction "2_2") (pintype "passive"))
      (node (ref "DA2") (pin "1") (pinfunction "CА_1") (pintype "passive"))
      (node (ref "R4") (pin "2") (pinfunction "2_2") (pintype "passive"))
      (node (ref "R6") (pin "2") (pinfunction "2_2") (pintype "passive"))
    )
    (net (code "12") (name "Net-(DD1-CONT)") (class "Default")
      (node (ref "C11") (pin "2") (pinfunction "2_2") (pintype "passive"))
      (node (ref "DD1") (pin "5") (pinfunction "CONT_5") (pintype "passive"))
    )
    (net (code "13") (name "Net-(DD1-DIS)") (class "Default")
      (node (ref "C10") (pin "2") (pinfunction "2_2") (pintype "passive"))
      (node (ref "DD1") (pin "6") (pinfunction "THR_6") (pintype "input"))
      (node (ref "DD1") (pin "7") (pinfunction "DIS_7") (pintype "open_collector"))
      (node (ref "R21") (pin "2") (pinfunction "2_2") (pintype "passive"))
    )
    (net (code "14") (name "Net-(DD1-OUT)") (class "Default")
      (node (ref "DD1") (pin "3") (pinfunction "OUT_3") (pintype "output"))
      (node (ref "R27") (pin "1") (pinfunction "1_1") (pintype "passive"))
      (node (ref "R29") (pin "1") (pinfunction "1_1") (pintype "passive"))
      (node (ref "R30") (pin "1") (pinfunction "1_1") (pintype "passive"))
    )
    (net (code "15") (name "Net-(DD1-TRIG)") (class "Default")
      (node (ref "C8") (pin "2") (pinfunction "2_2") (pintype "passive"))
      (node (ref "DD1") (pin "2") (pinfunction "TRIG_2") (pintype "input"))
      (node (ref "R19") (pin "2") (pinfunction "2_2") (pintype "passive"))
      (node (ref "R20") (pin "2") (pinfunction "2_2") (pintype "passive"))
    )
    (net (code "16") (name "Net-(HL1-К)") (class "Default")
      (node (ref "HL1") (pin "2") (pinfunction "К_2") (pintype "passive"))
      (node (ref "R27") (pin "2") (pinfunction "2_2") (pintype "passive"))
    )
    (net (code "17") (name "Net-(HL2-А)") (class "Default")
      (node (ref "HL2") (pin "1") (pinfunction "А_1") (pintype "passive"))
      (node (ref "R29") (pin "2") (pinfunction "2_2") (pintype "passive"))
    )
    (net (code "18") (name "Net-(R13-Pad2)") (class "Default")
      (node (ref "R13") (pin "2") (pinfunction "2_2") (pintype "passive"))
      (node (ref "R16") (pin "1") (pinfunction "1_1") (pintype "passive"))
      (node (ref "R16") (pin "2") (pinfunction "2_2") (pintype "passive"))
    )
    (net (code "19") (name "Net-(VD1-AC)") (class "Default")
      (node (ref "VD1") (pin "2") (pinfunction "AC_2") (pintype "passive"))
      (node (ref "VT6") (pin "1") (pinfunction "Б_1") (pintype "passive"))
      (node (ref "VT7") (pin "2") (pinfunction "К_2") (pintype "passive"))
      (node (ref "VT8") (pin "2") (pinfunction "К_2") (pintype "passive"))
    )
    (net (code "20") (name "Net-(VD1-C)") (class "Default")
      (node (ref "VD1") (pin "1") (pinfunction "А1_1") (pintype "passive"))
      (node (ref "VD1") (pin "3") (pinfunction "C_3") (pintype "passive"))
      (node (ref "VT1") (pin "2") (pinfunction "К_2") (pintype "passive"))
      (node (ref "VT3") (pin "2") (pinfunction "К_2") (pintype "passive"))
      (node (ref "VT4") (pin "1") (pinfunction "Б_1") (pintype "passive"))
    )
    (net (code "21") (name "Net-(VD2-А)") (class "Default")
      (node (ref "C14") (pin "2") (pinfunction "2_2") (pintype "passive"))
      (node (ref "C17") (pin "1") (pinfunction "1_1") (pintype "passive"))
      (node (ref "R32") (pin "2") (pinfunction "2_2") (pintype "passive"))
      (node (ref "VD2") (pin "1") (pinfunction "А_1") (pintype "passive"))
      (node (ref "VT12") (pin "3") (pinfunction "Э_3") (pintype "passive"))
      (node (ref "VT9") (pin "3") (pinfunction "Э_3") (pintype "passive"))
    )
    (net (code "22") (name "Net-(VD2-К)") (class "Default")
      (node (ref "C13") (pin "2") (pinfunction "2_2") (pintype "passive"))
      (node (ref "C16") (pin "1") (pinfunction "1_1") (pintype "passive"))
      (node (ref "R28") (pin "1") (pinfunction "1_1") (pintype "passive"))
      (node (ref "R31") (pin "2") (pinfunction "2_2") (pintype "passive"))
      (node (ref "VD2") (pin "2") (pinfunction "К_2") (pintype "passive"))
      (node (ref "VD3") (pin "2") (pinfunction "К_2") (pintype "passive"))
      (node (ref "VT11") (pin "3") (pinfunction "Э_3") (pintype "passive"))
    )
    (net (code "23") (name "Net-(VD4-К)") (class "Default")
      (node (ref "C12") (pin "2") (pinfunction "2_2") (pintype "passive"))
      (node (ref "R26") (pin "2") (pinfunction "2_2") (pintype "passive"))
      (node (ref "VD4") (pin "2") (pinfunction "К_2") (pintype "passive"))
      (node (ref "VT9") (pin "1") (pinfunction "Б_1") (pintype "passive"))
    )
    (net (code "24") (name "Net-(VD5-К)") (class "Default")
      (node (ref "R28") (pin "2") (pinfunction "2_2") (pintype "passive"))
      (node (ref "VD5") (pin "2") (pinfunction "К_2") (pintype "passive"))
    )
    (net (code "25") (name "Net-(VD6-А)") (class "Default")
      (node (ref "R34") (pin "1") (pinfunction "1_1") (pintype "passive"))
      (node (ref "VD6") (pin "1") (pinfunction "А_1") (pintype "passive"))
      (node (ref "VT11") (pin "2") (pinfunction "К_2") (pintype "passive"))
    )
    (net (code "26") (name "Net-(VD6-К)") (class "Default")
      (node (ref "R31") (pin "1") (pinfunction "1_1") (pintype "passive"))
      (node (ref "VD6") (pin "2") (pinfunction "К_2") (pintype "passive"))
      (node (ref "VT11") (pin "1") (pinfunction "Б_1") (pintype "passive"))
      (node (ref "VT6") (pin "2") (pinfunction "К_2") (pintype "passive"))
    )
    (net (code "27") (name "Net-(VD7-А)") (class "Default")
      (node (ref "R35") (pin "1") (pinfunction "1_1") (pintype "passive"))
      (node (ref "VD7") (pin "1") (pinfunction "А_1") (pintype "passive"))
      (node (ref "VT12") (pin "2") (pinfunction "К_2") (pintype "passive"))
    )
    (net (code "28") (name "Net-(VD7-К)") (class "Default")
      (node (ref "R32") (pin "1") (pinfunction "1_1") (pintype "passive"))
      (node (ref "VD7") (pin "2") (pinfunction "К_2") (pintype "passive"))
      (node (ref "VT12") (pin "1") (pinfunction "Б_1") (pintype "passive"))
      (node (ref "VT4") (pin "2") (pinfunction "К_2") (pintype "passive"))
    )
    (net (code "29") (name "Net-(VD8-А)") (class "Default")
      (node (ref "R33") (pin "1") (pinfunction "1_1") (pintype "passive"))
      (node (ref "VD8") (pin "1") (pinfunction "А_1") (pintype "passive"))
      (node (ref "VT10") (pin "2") (pinfunction "К_2") (pintype "passive"))
    )
    (net (code "30") (name "Net-(VD8-К)") (class "Default")
      (node (ref "R36") (pin "2") (pinfunction "2_2") (pintype "passive"))
      (node (ref "VD8") (pin "2") (pinfunction "К_2") (pintype "passive"))
      (node (ref "VT13") (pin "1") (pinfunction "Б_1") (pintype "passive"))
    )
    (net (code "31") (name "Net-(VD9-А)") (class "Default")
      (node (ref "R34") (pin "2") (pinfunction "2_2") (pintype "passive"))
      (node (ref "R37") (pin "2") (pinfunction "2_2") (pintype "passive"))
      (node (ref "VD9") (pin "1") (pinfunction "А_1") (pintype "passive"))
      (node (ref "VT14") (pin "1") (pinfunction "Б_1") (pintype "passive"))
    )
    (net (code "32") (name "Net-(VD9-К)") (class "Default")
      (node (ref "R39") (pin "1") (pinfunction "1_1") (pintype "passive"))
      (node (ref "VD9") (pin "2") (pinfunction "К_2") (pintype "passive"))
      (node (ref "VT14") (pin "3") (pinfunction "Э_3") (pintype "passive"))
    )
    (net (code "33") (name "Net-(VD10-А)") (class "Default")
      (node (ref "R35") (pin "2") (pinfunction "2_2") (pintype "passive"))
      (node (ref "R38") (pin "2") (pinfunction "2_2") (pintype "passive"))
      (node (ref "VD10") (pin "1") (pinfunction "А_1") (pintype "passive"))
      (node (ref "VT15") (pin "1") (pinfunction "Б_1") (pintype "passive"))
    )
    (net (code "34") (name "Net-(VD10-К)") (class "Default")
      (node (ref "R40") (pin "1") (pinfunction "1_1") (pintype "passive"))
      (node (ref "VD10") (pin "2") (pinfunction "К_2") (pintype "passive"))
      (node (ref "VT15") (pin "3") (pinfunction "Э_3") (pintype "passive"))
    )
    (net (code "35") (name "Net-(VD11-К)") (class "Default")
      (node (ref "C22") (pin "2") (pinfunction "2_2") (pintype "passive"))
      (node (ref "R43") (pin "1") (pinfunction "1_1") (pintype "passive"))
      (node (ref "VD11") (pin "2") (pinfunction "К_2") (pintype "passive"))
      (node (ref "VT17") (pin "1") (pinfunction "Б_1") (pintype "passive"))
    )
    (net (code "36") (name "Net-(VT1-Б)") (class "Default")
      (node (ref "R12") (pin "2") (pinfunction "2_2") (pintype "passive"))
      (node (ref "R13") (pin "1") (pinfunction "1_1") (pintype "passive"))
      (node (ref "VT1") (pin "1") (pinfunction "Б_1") (pintype "passive"))
      (node (ref "VT4") (pin "3") (pinfunction "Э_3") (pintype "passive"))
      (node (ref "VT6") (pin "3") (pinfunction "Э_3") (pintype "passive"))
      (node (ref "VT8") (pin "1") (pinfunction "Б_1") (pintype "passive"))
    )
    (net (code "37") (name "Net-(VT1-Э)") (class "Default")
      (node (ref "R9") (pin "2") (pinfunction "2_2") (pintype "passive"))
      (node (ref "VT1") (pin "3") (pinfunction "Э_3") (pintype "passive"))
    )
    (net (code "38") (name "Net-(VT2-Б)") (class "Default")
      (node (ref "R14") (pin "1") (pinfunction "1_1") (pintype "passive"))
      (node (ref "VT2") (pin "1") (pinfunction "Б_1") (pintype "passive"))
      (node (ref "VT5") (pin "3") (pinfunction "Э_3") (pintype "passive"))
    )
    (net (code "39") (name "Net-(VT2-К)") (class "Default")
      (node (ref "R1") (pin "1") (pinfunction "1_1") (pintype "passive"))
      (node (ref "R8") (pin "1") (pinfunction "1_1") (pintype "passive"))
      (node (ref "VT2") (pin "2") (pinfunction "К_2") (pintype "passive"))
      (node (ref "VT5") (pin "1") (pinfunction "Б_1") (pintype "passive"))
    )
    (net (code "40") (name "Net-(VT2-Э)") (class "Default")
      (node (ref "C6") (pin "2") (pinfunction "2_2") (pintype "passive"))
      (node (ref "R14") (pin "2") (pinfunction "2_2") (pintype "passive"))
      (node (ref "R24") (pin "1") (pinfunction "1_1") (pintype "passive"))
      (node (ref "R8") (pin "2") (pinfunction "2_2") (pintype "passive"))
      (node (ref "VT2") (pin "3") (pinfunction "Э_3") (pintype "passive"))
    )
    (net (code "41") (name "Net-(VT3-Б)") (class "Default")
      (node (ref "C2") (pin "2") (pinfunction "2_2") (pintype "passive"))
      (node (ref "R2") (pin "2") (pinfunction "2_2") (pintype "passive"))
      (node (ref "R7") (pin "2") (pinfunction "2_2") (pintype "passive"))
      (node (ref "VT3") (pin "1") (pinfunction "Б_1") (pintype "passive"))
    )
    (net (code "42") (name "Net-(VT3-Э)") (class "Default")
      (node (ref "R10") (pin "1") (pinfunction "1_1") (pintype "passive"))
      (node (ref "R11") (pin "3") (pinfunction "3_3") (pintype "passive"))
      (node (ref "VT3") (pin "3") (pinfunction "Э_3") (pintype "passive"))
    )
    (net (code "43") (name "Net-(VT5-К)") (class "Default")
      (node (ref "R10") (pin "2") (pinfunction "2_2") (pintype "passive"))
      (node (ref "R11") (pin "2") (pinfunction "2_2") (pintype "passive"))
      (node (ref "R15") (pin "1") (pinfunction "1_1") (pintype "passive"))
      (node (ref "VT5") (pin "2") (pinfunction "К_2") (pintype "passive"))
    )
    (net (code "44") (name "Net-(VT7-Б)") (class "Default")
      (node (ref "C5") (pin "2") (pinfunction "2_2") (pintype "passive"))
      (node (ref "R18") (pin "2") (pinfunction "2_2") (pintype "passive"))
      (node (ref "R22") (pin "1") (pinfunction "1_1") (pintype "passive"))
      (node (ref "R23") (pin "1") (pinfunction "1_1") (pintype "passive"))
      (node (ref "VT7") (pin "1") (pinfunction "Б_1") (pintype "passive"))
    )
    (net (code "45") (name "Net-(VT7-Э)") (class "Default")
      (node (ref "R11") (pin "1") (pinfunction "1_1") (pintype "passive"))
      (node (ref "R15") (pin "2") (pinfunction "2_2") (pintype "passive"))
      (node (ref "VT7") (pin "3") (pinfunction "Э_3") (pintype "passive"))
    )
    (net (code "46") (name "Net-(VT8-Э)") (class "Default")
      (node (ref "R17") (pin "2") (pinfunction "2_2") (pintype "passive"))
      (node (ref "VT8") (pin "3") (pinfunction "Э_3") (pintype "passive"))
    )
    (net (code "47") (name "Net-(VT10-Б)") (class "Default")
      (node (ref "R30") (pin "2") (pinfunction "2_2") (pintype "passive"))
      (node (ref "VT10") (pin "1") (pinfunction "Б_1") (pintype "passive"))
    )
    (net (code "48") (name "Net-(VT16-G1)") (class "Default")
      (node (ref "R39") (pin "2") (pinfunction "2_2") (pintype "passive"))
      (node (ref "VT16") (pin "4") (pinfunction "G1_4") (pintype "passive"))
    )
    (net (code "49") (name "Net-(VT16-G2)") (class "Default")
      (node (ref "R40") (pin "2") (pinfunction "2_2") (pintype "passive"))
      (node (ref "VT16") (pin "2") (pinfunction "G2_2") (pintype "passive"))
    )
    (net (code "50") (name "OUT") (class "Default")
      (node (ref "C13") (pin "1") (pinfunction "1_1") (pintype "passive"))
      (node (ref "C16") (pin "2") (pinfunction "2_2") (pintype "passive"))
      (node (ref "L1") (pin "1") (pinfunction "1_1") (pintype "passive"))
      (node (ref "R37") (pin "1") (pinfunction "1_1") (pintype "passive"))
      (node (ref "R44") (pin "1") (pinfunction "1_1") (pintype "passive"))
      (node (ref "R45") (pin "2") (pinfunction "2_2") (pintype "passive"))
      (node (ref "VD3") (pin "1") (pinfunction "А_1") (pintype "passive"))
      (node (ref "VT14") (pin "2") (pinfunction "К_2") (pintype "passive"))
      (node (ref "VT16") (pin "3") (pinfunction "S1D2_3") (pintype "passive"))
    )
    (net (code "51") (name "OUT_LP") (class "Default")
      (node (ref "C30") (pin "2") (pinfunction "2_2") (pintype "passive"))
      (node (ref "C9") (pin "2") (pinfunction "2_2") (pintype "passive"))
      (node (ref "L1") (pin "2") (pinfunction "2_2") (pintype "passive"))
      (node (ref "R22") (pin "2") (pinfunction "2_2") (pintype "passive"))
      (node (ref "XT2") (pin "1") (pintype "passive"))
    )
    (net (code "52") (name "VCC") (class "Default")
      (node (ref "C25") (pin "1") (pinfunction "1_1") (pintype "passive"))
      (node (ref "C27") (pin "1") (pinfunction "1_1") (pintype "passive"))
      (node (ref "R24") (pin "2") (pinfunction "2_2") (pintype "passive"))
      (node (ref "R3") (pin "1") (pinfunction "1_1") (pintype "passive"))
      (node (ref "R41") (pin "2") (pinfunction "2_2") (pintype "passive"))
      (node (ref "R43") (pin "2") (pinfunction "2_2") (pintype "passive"))
      (node (ref "VD5") (pin "1") (pinfunction "А_1") (pintype "passive"))
      (node (ref "VT17") (pin "2") (pinfunction "К_2") (pintype "passive"))
      (node (ref "XT1") (pin "1") (pintype "passive"))
    )
    (net (code "53") (name "VCC12P0") (class "Default")
      (node (ref "C15") (pin "2") (pinfunction "2_2") (pintype "passive"))
      (node (ref "C29") (pin "2") (pinfunction "2_2") (pintype "passive"))
      (node (ref "DD1") (pin "4") (pinfunction "~{RES}_4") (pintype "input"))
      (node (ref "DD1") (pin "8") (pinfunction "VCC_8") (pintype "power_in"))
      (node (ref "HL1") (pin "1") (pinfunction "А_1") (pintype "passive"))
      (node (ref "R20") (pin "1") (pinfunction "1_1") (pintype "passive"))
      (node (ref "R21") (pin "1") (pinfunction "1_1") (pintype "passive"))
      (node (ref "R33") (pin "2") (pinfunction "2_2") (pintype "passive"))
      (node (ref "VT17") (pin "3") (pinfunction "Э_3") (pintype "passive"))
    )
    (net (code "54") (name "VCC_PROT") (class "Default")
      (node (ref "C18") (pin "1") (pinfunction "1_1") (pintype "passive"))
      (node (ref "C19") (pin "1") (pinfunction "1_1") (pintype "passive"))
      (node (ref "C23") (pin "1") (pinfunction "1_1") (pintype "passive"))
      (node (ref "C3") (pin "1") (pinfunction "1_1") (pintype "passive"))
      (node (ref "DA1") (pin "2") (pinfunction "CК_2") (pintype "passive"))
      (node (ref "R41") (pin "1") (pinfunction "1_1") (pintype "passive"))
      (node (ref "R5") (pin "1") (pinfunction "1_1") (pintype "passive"))
      (node (ref "VT16") (pin "5") (pinfunction "D1_5") (pintype "passive"))
    )
    (net (code "55") (name "VSS") (class "Default")
      (node (ref "C26") (pin "2") (pinfunction "2_2") (pintype "passive"))
      (node (ref "C28") (pin "2") (pinfunction "2_2") (pintype "passive"))
      (node (ref "C4") (pin "1") (pinfunction "1_1") (pintype "passive"))
      (node (ref "DA2") (pin "2") (pinfunction "CК_2") (pintype "passive"))
      (node (ref "R25") (pin "2") (pinfunction "2_2") (pintype "passive"))
      (node (ref "R42") (pin "1") (pinfunction "1_1") (pintype "passive"))
      (node (ref "R6") (pin "1") (pinfunction "1_1") (pintype "passive"))
      (node (ref "XT5") (pin "1") (pintype "passive"))
    )
    (net (code "56") (name "VSS_PROT") (class "Default")
      (node (ref "C12") (pin "1") (pinfunction "1_1") (pintype "passive"))
      (node (ref "C14") (pin "1") (pinfunction "1_1") (pintype "passive"))
      (node (ref "C17") (pin "2") (pinfunction "2_2") (pintype "passive"))
      (node (ref "C20") (pin "1") (pinfunction "1_1") (pintype "passive"))
      (node (ref "C21") (pin "2") (pinfunction "2_2") (pintype "passive"))
      (node (ref "C24") (pin "1") (pinfunction "1_1") (pintype "passive"))
      (node (ref "R38") (pin "1") (pinfunction "1_1") (pintype "passive"))
      (node (ref "R4") (pin "1") (pinfunction "1_1") (pintype "passive"))
      (node (ref "R42") (pin "2") (pinfunction "2_2") (pintype "passive"))
      (node (ref "VD4") (pin "1") (pinfunction "А_1") (pintype "passive"))
      (node (ref "VT15") (pin "2") (pinfunction "К_2") (pintype "passive"))
      (node (ref "VT16") (pin "1") (pinfunction "S2_1") (pintype "passive"))
    )
  )
)
